# UniversalBoardBreakout.net
KiCad netlist of a schematic drawn in EAGLE
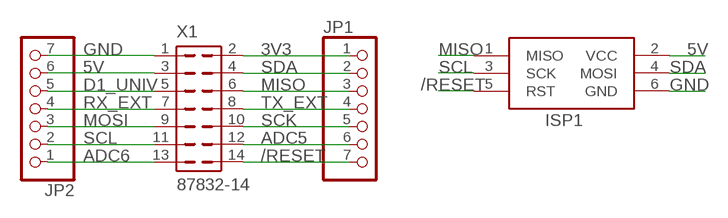
[diagram p0: schematic, sheet 1]

(export (version "E")
  (design (tool "Eeschema 10.0.6"))
  (components
    (comp (ref "ISP1")
      (value "AVRISP-6")
      (footprint "eagle-import:AVRISP")
      (libsource (lib "eagle-import") (part "AVRISP-6"))
    )
    (comp (ref "JP1")
      (value "CONN_7")
      (footprint "eagle-import:1X07")
      (libsource (lib "eagle-import") (part "CONN_7"))
    )
    (comp (ref "JP2")
      (value "CONN_7")
      (footprint "eagle-import:1X07")
      (libsource (lib "eagle-import") (part "CONN_7"))
    )
    (comp (ref "X1")
      (value "87832-14")
      (footprint "eagle-import:87832-14")
      (fields (field (name "MF") "MOLEX"))
      (libsource (lib "eagle-import") (part "87832-14"))
    )
  )
  (nets
    (net (code "1") (name "/3V3") (class "Default")
      (node (ref "JP1") (pin "1") (pinfunction "1_1") (pintype "passive"))
      (node (ref "X1") (pin "2") (pinfunction "2_2") (pintype "passive"))
    )
    (net (code "2") (name "/5V") (class "Default")
      (node (ref "ISP1") (pin "2") (pinfunction "VCC_2") (pintype "power_in"))
      (node (ref "JP2") (pin "6") (pinfunction "6_6") (pintype "passive"))
      (node (ref "X1") (pin "3") (pinfunction "3_3") (pintype "passive"))
    )
    (net (code "3") (name "/ADC5") (class "Default")
      (node (ref "JP1") (pin "6") (pinfunction "6_6") (pintype "passive"))
      (node (ref "X1") (pin "12") (pinfunction "12_12") (pintype "passive"))
    )
    (net (code "4") (name "/ADC6") (class "Default")
      (node (ref "JP2") (pin "1") (pinfunction "1_1") (pintype "passive"))
      (node (ref "X1") (pin "13") (pinfunction "13_13") (pintype "passive"))
    )
    (net (code "5") (name "/D1_UNIV") (class "Default")
      (node (ref "JP2") (pin "5") (pinfunction "5_5") (pintype "passive"))
      (node (ref "X1") (pin "5") (pinfunction "5_5") (pintype "passive"))
    )
    (net (code "6") (name "/GND") (class "Default")
      (node (ref "ISP1") (pin "6") (pinfunction "GND_6") (pintype "power_in"))
      (node (ref "JP2") (pin "7") (pinfunction "7_7") (pintype "passive"))
      (node (ref "X1") (pin "1") (pinfunction "1_1") (pintype "passive"))
    )
    (net (code "7") (name "/MISO") (class "Default")
      (node (ref "ISP1") (pin "1") (pinfunction "MISO_1") (pintype "input"))
      (node (ref "JP1") (pin "3") (pinfunction "3_3") (pintype "passive"))
      (node (ref "X1") (pin "6") (pinfunction "6_6") (pintype "passive"))
    )
    (net (code "8") (name "/MOSI") (class "Default")
      (node (ref "JP2") (pin "3") (pinfunction "3_3") (pintype "passive"))
      (node (ref "X1") (pin "9") (pinfunction "9_9") (pintype "passive"))
    )
    (net (code "9") (name "/RX_EXT") (class "Default")
      (node (ref "JP2") (pin "4") (pinfunction "4_4") (pintype "passive"))
      (node (ref "X1") (pin "7") (pinfunction "7_7") (pintype "passive"))
    )
    (net (code "10") (name "/SCK") (class "Default")
      (node (ref "JP1") (pin "5") (pinfunction "5_5") (pintype "passive"))
      (node (ref "X1") (pin "10") (pinfunction "10_10") (pintype "passive"))
    )
    (net (code "11") (name "/SCL") (class "Default")
      (node (ref "ISP1") (pin "3") (pinfunction "SCK_3") (pintype "output"))
      (node (ref "JP2") (pin "2") (pinfunction "2_2") (pintype "passive"))
      (node (ref "X1") (pin "11") (pinfunction "11_11") (pintype "passive"))
    )
    (net (code "12") (name "/SDA") (class "Default")
      (node (ref "ISP1") (pin "4") (pinfunction "MOSI_4") (pintype "output"))
      (node (ref "JP1") (pin "2") (pinfunction "2_2") (pintype "passive"))
      (node (ref "X1") (pin "4") (pinfunction "4_4") (pintype "passive"))
    )
    (net (code "13") (name "/TX_EXT") (class "Default")
      (node (ref "JP1") (pin "4") (pinfunction "4_4") (pintype "passive"))
      (node (ref "X1") (pin "8") (pinfunction "8_8") (pintype "passive"))
    )
    (net (code "14") (name "/{slash}RESET") (class "Default")
      (node (ref "ISP1") (pin "5") (pinfunction "RST_5") (pintype "output"))
      (node (ref "JP1") (pin "7") (pinfunction "7_7") (pintype "passive"))
      (node (ref "X1") (pin "14") (pinfunction "14_14") (pintype "passive"))
    )
  )
)
